# SAMW25_Xplained_Pro_triple_input_power_s.net
KiCad netlist of a schematic drawn in Altium Designer
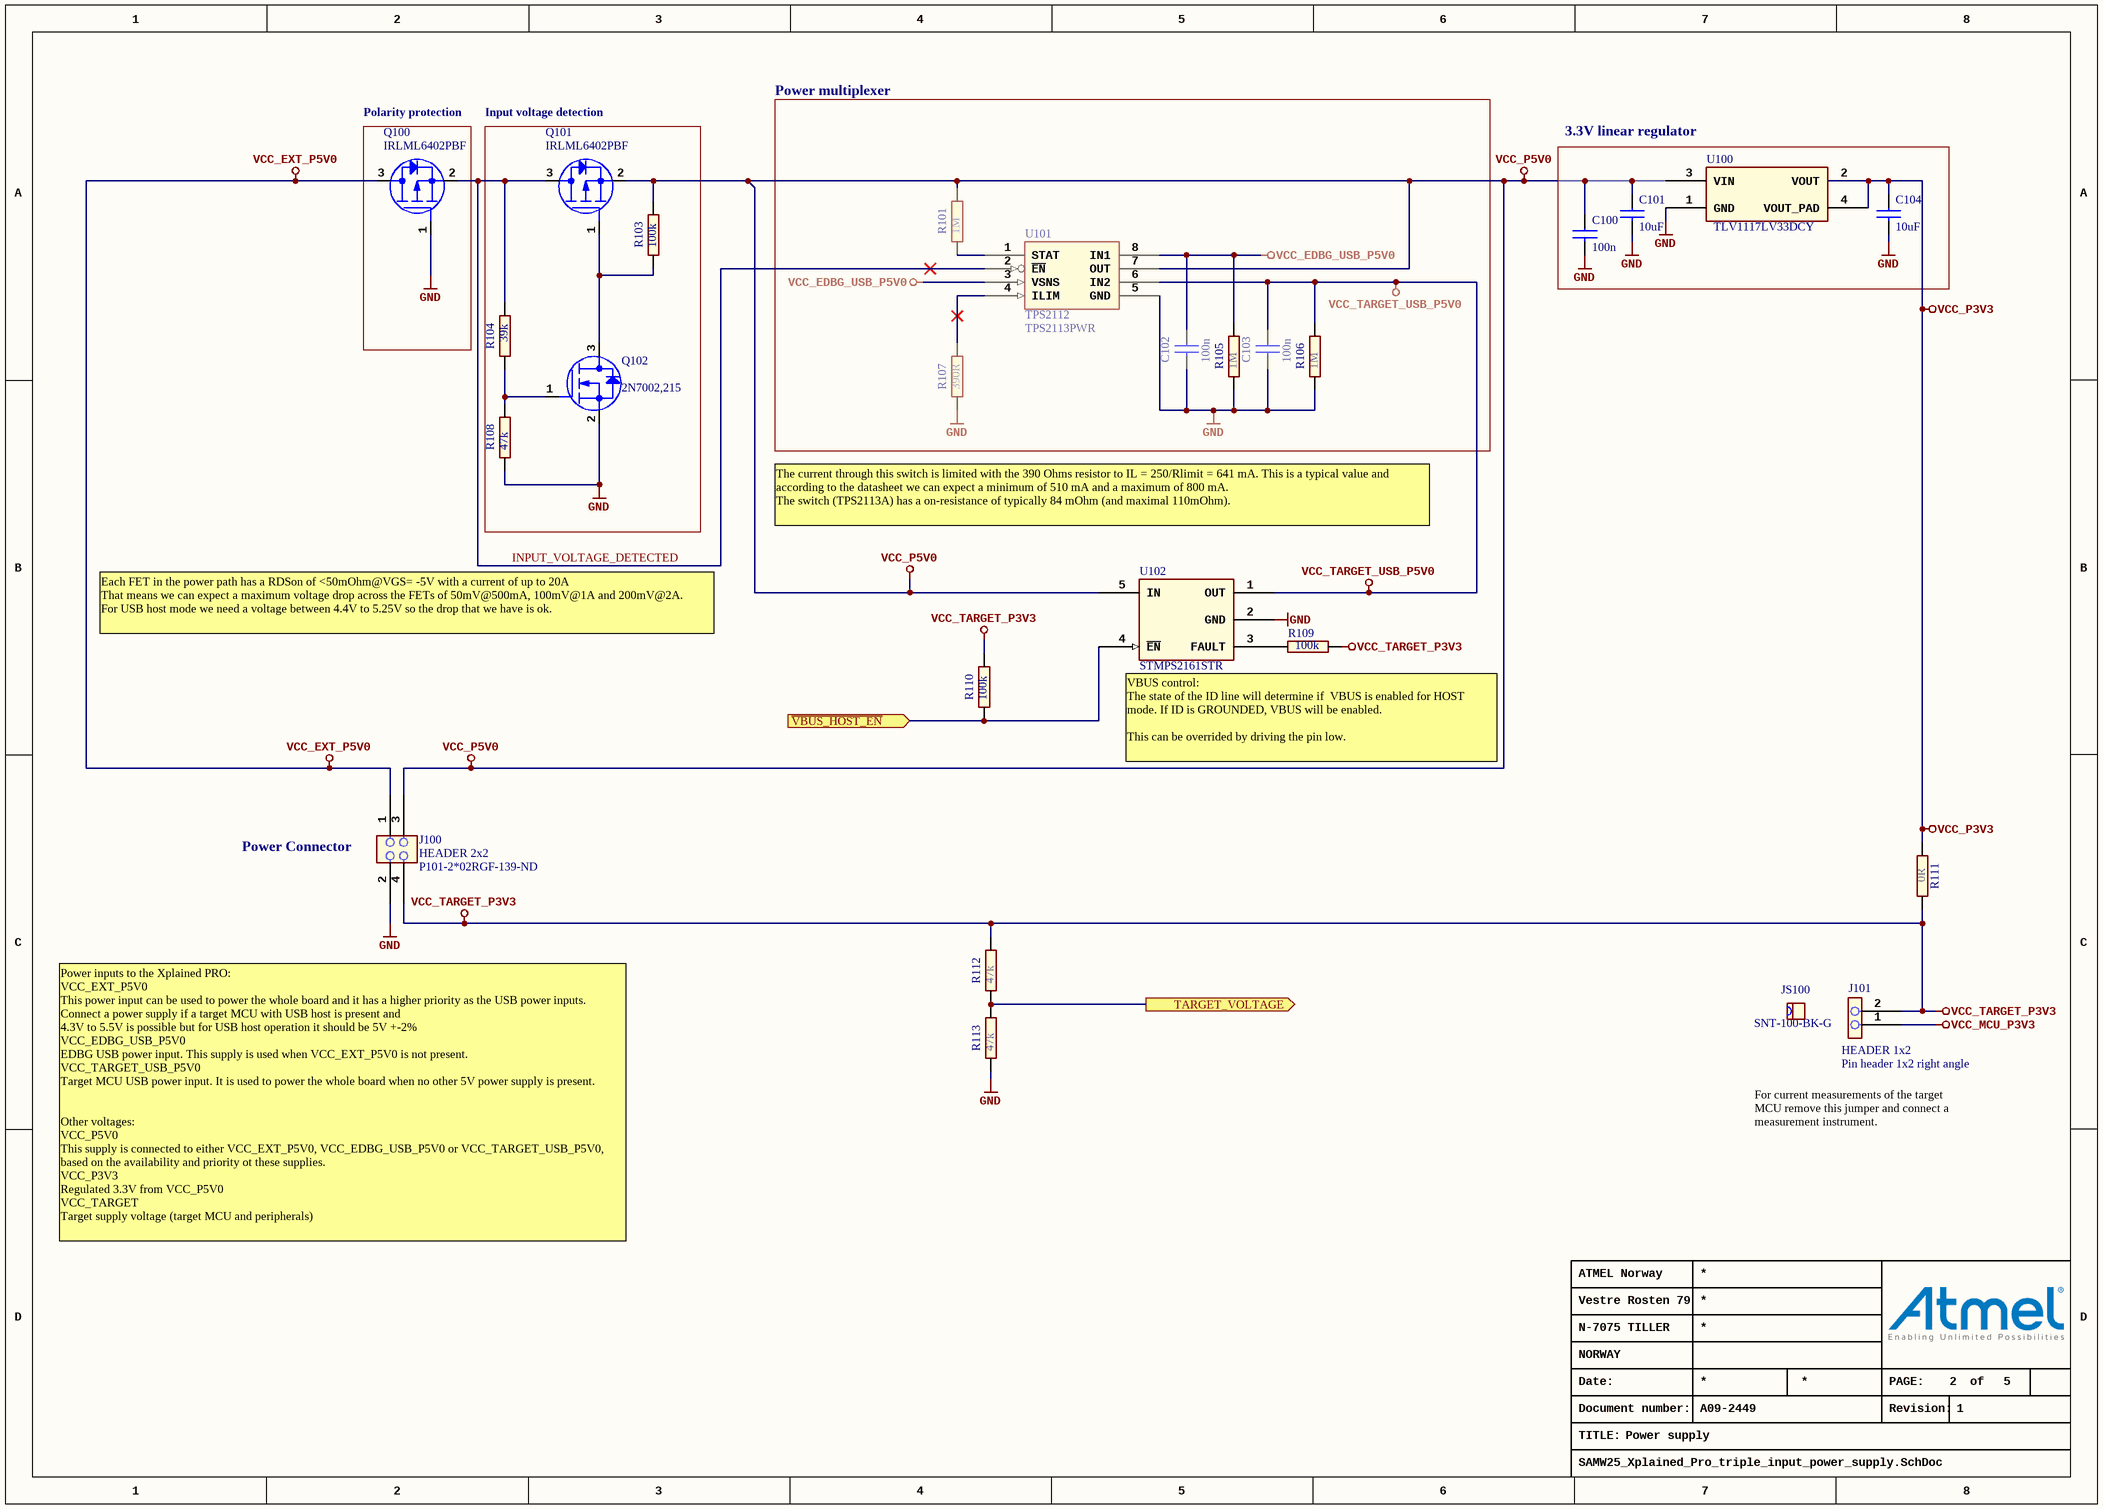
[diagram p0: SAMW25_Xplained_Pro_triple_input_power_supply.SchDoc]

(export (version "E")
  (design (tool "Eeschema 10.0.6"))
  (components
    (comp (ref "C100")
      (value "100n")
      (footprint "AP1-00001")
      (description "Ceramic capacitor, SMD 0402, X7R, 16V, +/-10%")
      (fields
        (field (name "TOLERANCE") "16V, +/-10%")
        (field (name "MANUFACTURER") "Kemet")
        (field (name "VERIFIED BY") "Lars Helge Mo")
      )
      (libsource (lib "AltiumDbLib") (part "CAP-NONPOL"))
    )
    (comp (ref "C101")
      (value "10uF")
      (footprint "AP1-00039")
      (description "Ceramic capacitor, SMD 0603, X5R, 16V, 10UF ± 20% (High Density)")
      (fields
        (field (name "TOLERANCE") "­± 20%")
        (field (name "MANUFACTURER") "Taiyo Yuden")
        (field (name "VERIFIED BY") "Lars Helge Mo")
      )
      (libsource (lib "AltiumDbLib") (part "CAP-NONPOL"))
    )
    (comp (ref "C102")
      (value "100n")
      (footprint "AP1-00053")
      (description "Ceramic capacitor, SMD 0402, X7R, 16V, +/-10%")
      (fields
        (field (name "TOLERANCE") "16V, +/-10%")
        (field (name "MANUFACTURER") "Kemet")
        (field (name "VERIFIED BY") "Lars Helge Mo")
      )
      (libsource (lib "AltiumDbLib") (part "CAP-NONPOL"))
    )
    (comp (ref "C103")
      (value "100n")
      (footprint "AP1-00053")
      (description "Ceramic capacitor, SMD 0402, X7R, 16V, +/-10%")
      (fields
        (field (name "TOLERANCE") "16V, +/-10%")
        (field (name "MANUFACTURER") "Kemet")
        (field (name "VERIFIED BY") "Lars Helge Mo")
      )
      (libsource (lib "AltiumDbLib") (part "CAP-NONPOL"))
    )
    (comp (ref "C104")
      (value "10uF")
      (footprint "AP1-00039")
      (description "Ceramic capacitor, SMD 0603, X5R, 16V, 10UF ± 20% (High Density)")
      (fields
        (field (name "TOLERANCE") "­± 20%")
        (field (name "MANUFACTURER") "Taiyo Yuden")
        (field (name "VERIFIED BY") "Lars Helge Mo")
      )
      (libsource (lib "AltiumDbLib") (part "CAP-NONPOL"))
    )
    (comp (ref "J100")
      (value "HEADER 2x2")
      (footprint "AP8-00628")
      (description "Pin header, 2x2, Right Angle, 2.54mm, THT, Pin In Paste")
      (fields
        (field (name "ALTIUM_VALUE") "P101-2*02RGF-139-ND")
        (field (name "MANUFACTURER") "Pro-data International Corp")
        (field (name "MPN") "P101-2*02RGF-139-ND")
        (field (name "VERIFIED BY") "Lars Helge Mo")
      )
      (libsource (lib "AltiumDbLib") (part "HEADER 2x2"))
    )
    (comp (ref "J101")
      (value "HEADER 1x2")
      (footprint "AP8-00367")
      (description "1x2 pin header, right angle, 2.54 mm pitch, through-hole")
      (fields
        (field (name "ALTIUM_VALUE") "Pin header 1x2 right angle")
        (field (name "MANUFACTURER") "Pro-data International Corp")
        (field (name "MPN") "2213R-2G")
        (field (name "VERIFIED BY") "Lars Helge")
      )
      (libsource (lib "AltiumDbLib") (part "HEADER 1x2"))
    )
    (comp (ref "JS100")
      (value "SNT-100-BK-G")
      (footprint "AP8-00525")
      (description "Jumper cap for 2.54mm pinheader")
      (fields
        (field (name "MANUFACTURER") "SAMTEC")
        (field (name "Comment") "To be used by request from ESCATEC")
        (field (name "VERIFIED BY") "Lars Helge Mo")
      )
      (libsource (lib "AltiumDbLib") (part "JUMPER_CAP"))
    )
    (comp (ref "Q100")
      (value "IRLML6402PBF")
      (footprint "AP5-00002")
      (description "P-ch. MOSFET. -30V, -3.7A continuous,RDS(ON)=0.05Ohm@VGS=-4,5V, RDS(ON)=0.08Ohm@VGS=-2.5V")
      (fields (field (name "MANUFACTURER") "International Rectifier") (field (name "Comment") "MOSFET_P_GSD"))
      (libsource (lib "AltiumDbLib") (part "MOSFET_P_GSD"))
    )
    (comp (ref "Q101")
      (value "IRLML6402PBF")
      (footprint "AP5-00002")
      (description "P-ch. MOSFET. -30V, -3.7A continuous,RDS(ON)=0.05Ohm@VGS=-4,5V, RDS(ON)=0.08Ohm@VGS=-2.5V")
      (fields (field (name "MANUFACTURER") "International Rectifier") (field (name "Comment") "MOSFET_P_GSD"))
      (libsource (lib "AltiumDbLib") (part "MOSFET_P_GSD"))
    )
    (comp (ref "Q102")
      (value "2N7002,215")
      (footprint "AP5-00002")
      (description "N-Channel MOSFET. 60V, 0.300A continuous, 1.2A Peak. RDS(ON) = 3.8Ohm@VGS=4.5V, VGS(th)<2.5V")
      (fields (field (name "MANUFACTURER") "NXP") (field (name "Comment") "MOSFET_N_GSD"))
      (libsource (lib "AltiumDbLib") (part "MOSFET_N_GSD"))
    )
    (comp (ref "R101")
      (value "1M")
      (footprint "AP2-00011")
      (description "Thick film resistor, SMD 0402, 1/16W, 1%")
      (fields
        (field (name "TOLERANCE") "1 %")
        (field (name "Comment") "R2")
        (field (name "VERIFIED BY") "Lars Helge Mo")
      )
      (libsource (lib "AltiumDbLib") (part "R2"))
    )
    (comp (ref "R103")
      (value "100k")
      (footprint "AP2-00011")
      (description "Thick film resistor, SMD 0402, 1/16W, 1%")
      (fields
        (field (name "TOLERANCE") "1 %")
        (field (name "Comment") "R2")
        (field (name "VERIFIED BY") "Lars Helge Mo")
      )
      (libsource (lib "AltiumDbLib") (part "R2"))
    )
    (comp (ref "R104")
      (value "39k")
      (footprint "AP2-00011")
      (description "Thick film resistor, SMD 0402, 1/16W, 1%")
      (fields
        (field (name "TOLERANCE") "1 %")
        (field (name "Comment") "R2")
        (field (name "VERIFIED BY") "Lars Helge Mo")
      )
      (libsource (lib "AltiumDbLib") (part "R2"))
    )
    (comp (ref "R105")
      (value "1M")
      (footprint "AP2-00011")
      (description "Thick film resistor, SMD 0402, 1/16W, 1%")
      (fields
        (field (name "TOLERANCE") "1 %")
        (field (name "Comment") "R2")
        (field (name "VERIFIED BY") "Lars Helge Mo")
      )
      (libsource (lib "AltiumDbLib") (part "R2"))
    )
    (comp (ref "R106")
      (value "1M")
      (footprint "AP2-00011")
      (description "Thick film resistor, SMD 0402, 1/16W, 1%")
      (fields
        (field (name "TOLERANCE") "1 %")
        (field (name "Comment") "R2")
        (field (name "VERIFIED BY") "Lars Helge Mo")
      )
      (libsource (lib "AltiumDbLib") (part "R2"))
    )
    (comp (ref "R107")
      (value "390R")
      (footprint "AP2-00011")
      (description "Thick film resistor, SMD 0402, 1/16W, 1%")
      (fields
        (field (name "TOLERANCE") "1 %")
        (field (name "Comment") "R2")
        (field (name "VERIFIED BY") "Lars Helge Mo")
      )
      (libsource (lib "AltiumDbLib") (part "R2"))
    )
    (comp (ref "R108")
      (value "47k")
      (footprint "AP2-00011")
      (description "Thick film resistor, SMD 0402, 1/16W, 1%")
      (fields
        (field (name "TOLERANCE") "1 %")
        (field (name "Comment") "R2")
        (field (name "VERIFIED BY") "Lars Helge Mo")
      )
      (libsource (lib "AltiumDbLib") (part "R2"))
    )
    (comp (ref "R109")
      (value "100k")
      (footprint "AP2-00011")
      (description "Thick film resistor, SMD 0402, 1/16W, 1%")
      (fields
        (field (name "TOLERANCE") "1 %")
        (field (name "Comment") "R2")
        (field (name "VERIFIED BY") "Lars Helge Mo")
      )
      (libsource (lib "") (part "R2_2"))
    )
    (comp (ref "R110")
      (value "100k")
      (footprint "AP2-00011")
      (description "Thick film resistor, SMD 0402, 1/16W, 1%")
      (fields
        (field (name "TOLERANCE") "1 %")
        (field (name "Comment") "R2")
        (field (name "VERIFIED BY") "Lars Helge Mo")
      )
      (libsource (lib "AltiumDbLib") (part "R2"))
    )
    (comp (ref "R111")
      (value "0R")
      (footprint "AP2-00011")
      (description "Thick film resistor, SMD 0402, 1/16W, 1%")
      (fields
        (field (name "TOLERANCE") "1 %")
        (field (name "Comment") "R2")
        (field (name "VERIFIED BY") "Lars Helge Mo")
      )
      (libsource (lib "") (part "R2_3"))
    )
    (comp (ref "R112")
      (value "47k")
      (footprint "AP2-00011")
      (description "Thick film resistor, SMD 0402, 1/16W, 1%")
      (fields
        (field (name "TOLERANCE") "1 %")
        (field (name "Comment") "R2")
        (field (name "VERIFIED BY") "Lars Helge Mo")
      )
      (libsource (lib "") (part "R2_1"))
    )
    (comp (ref "R113")
      (value "47k")
      (footprint "AP2-00011")
      (description "Thick film resistor, SMD 0402, 1/16W, 1%")
      (fields
        (field (name "TOLERANCE") "1 %")
        (field (name "Comment") "R2")
        (field (name "VERIFIED BY") "Lars Helge Mo")
      )
      (libsource (lib "") (part "R2_1"))
    )
    (comp (ref "U100")
      (value "TLV1117LV33DCY")
      (footprint "AP6-00399")
      (description "1-A, LDO (0.455V @ 1A), 3.3V out, 1.5% accuracy, 6.0V Vin max.")
      (fields (field (name "MANUFACTURER") "Texas Instruments") (field (name "MPN") "TLV1117LV33DCYR"))
      (libsource (lib "AltiumDbLib") (part "VOLTREG_SOT223_4"))
    )
    (comp (ref "U101")
      (value "TPS2112")
      (footprint "AP6-00054")
      (description "Autoswitching 2:1 Power Mux")
      (fields
        (field (name "ALTIUM_VALUE") "TPS2113PWR")
        (field (name "MANUFACTURER") "Texas Instruments")
        (field (name "MPN") "TPS2113PWR")
        (field (name "VERIFIED BY") "Sveinung Helgeland")
      )
      (libsource (lib "AltiumDbLib") (part "TPS2112"))
    )
    (comp (ref "U102")
      (value "STMPS2161STR")
      (footprint "AP6-00087")
      (description "Single channel power switch, 1A, reverse block, active low enabled.")
      (fields
        (field (name "TOLERANCE") "2.7 to 5.5V")
        (field (name "Comment") "STMPS2161")
        (field (name "VERIFIED BY") "*")
      )
      (libsource (lib "AltiumDbLib") (part "STMPS2161"))
    )
  )
  (nets
    (net (code "1") (name "/INPUT_VOLTAGE_DETECTED") (class "Default")
      (node (ref "Q100") (pin "2") (pinfunction "S_2") (pintype "passive"))
      (node (ref "Q101") (pin "3") (pinfunction "D_3") (pintype "passive"))
      (node (ref "R104") (pin "2") (pinfunction "2_2") (pintype "passive"))
      (node (ref "U101") (pin "2") (pinfunction "~{EN}_2") (pintype "input"))
    )
    (net (code "2") (name "/TARGET_VOLTAGE") (class "Default")
      (node (ref "R112") (pin "1") (pinfunction "1_1") (pintype "passive"))
      (node (ref "R113") (pin "2") (pinfunction "2_2") (pintype "passive"))
    )
    (net (code "3") (name "/~{VBUS_HOST_EN}") (class "Default")
      (node (ref "R110") (pin "1") (pinfunction "1_1") (pintype "passive"))
      (node (ref "U102") (pin "4") (pinfunction "~{EN}_4") (pintype "input"))
    )
    (net (code "4") (name "GND") (class "Default")
      (node (ref "C100") (pin "2") (pinfunction "2_2") (pintype "passive"))
      (node (ref "C101") (pin "2") (pinfunction "2_2") (pintype "passive"))
      (node (ref "C102") (pin "2") (pinfunction "2_2") (pintype "passive"))
      (node (ref "C103") (pin "2") (pinfunction "2_2") (pintype "passive"))
      (node (ref "C104") (pin "2") (pinfunction "2_2") (pintype "passive"))
      (node (ref "J100") (pin "2") (pinfunction "2_2") (pintype "passive"))
      (node (ref "Q100") (pin "1") (pinfunction "G_1") (pintype "passive"))
      (node (ref "Q102") (pin "2") (pinfunction "S_2") (pintype "passive"))
      (node (ref "R105") (pin "1") (pinfunction "1_1") (pintype "passive"))
      (node (ref "R106") (pin "1") (pinfunction "1_1") (pintype "passive"))
      (node (ref "R107") (pin "1") (pinfunction "1_1") (pintype "passive"))
      (node (ref "R108") (pin "1") (pinfunction "1_1") (pintype "passive"))
      (node (ref "R113") (pin "1") (pinfunction "1_1") (pintype "passive"))
      (node (ref "U100") (pin "1") (pinfunction "GND_1") (pintype "power_in"))
      (node (ref "U101") (pin "5") (pinfunction "GND_5") (pintype "power_in"))
      (node (ref "U102") (pin "2") (pinfunction "GND_2") (pintype "power_in"))
    )
    (net (code "5") (name "Net-(Q101-G)") (class "Default")
      (node (ref "Q101") (pin "1") (pinfunction "G_1") (pintype "passive"))
      (node (ref "Q102") (pin "3") (pinfunction "D_3") (pintype "passive"))
      (node (ref "R103") (pin "1") (pinfunction "1_1") (pintype "passive"))
    )
    (net (code "6") (name "Net-(Q102-G)") (class "Default")
      (node (ref "Q102") (pin "1") (pinfunction "G_1") (pintype "passive"))
      (node (ref "R104") (pin "1") (pinfunction "1_1") (pintype "passive"))
      (node (ref "R108") (pin "2") (pinfunction "2_2") (pintype "passive"))
    )
    (net (code "7") (name "Net-(U101-ILIM)") (class "Default")
      (node (ref "R107") (pin "2") (pinfunction "2_2") (pintype "passive"))
      (node (ref "U101") (pin "4") (pinfunction "ILIM_4") (pintype "input"))
    )
    (net (code "8") (name "Net-(U101-STAT)") (class "Default")
      (node (ref "R101") (pin "1") (pinfunction "1_1") (pintype "passive"))
      (node (ref "U101") (pin "1") (pinfunction "STAT_1") (pintype "open_collector"))
    )
    (net (code "9") (name "Net-(U102-FAULT)") (class "Default")
      (node (ref "R109") (pin "2") (pinfunction "2_2") (pintype "passive"))
      (node (ref "U102") (pin "3") (pinfunction "FAULT_3") (pintype "open_collector"))
    )
    (net (code "10") (name "VCC_EDBG_USB_P5V0") (class "Default")
      (node (ref "C102") (pin "1") (pinfunction "1_1") (pintype "passive"))
      (node (ref "R105") (pin "2") (pinfunction "2_2") (pintype "passive"))
      (node (ref "U101") (pin "3") (pinfunction "VSNS_3") (pintype "input"))
      (node (ref "U101") (pin "8") (pinfunction "IN1_8") (pintype "power_in"))
    )
    (net (code "11") (name "VCC_EXT_P5V0") (class "Default")
      (node (ref "J100") (pin "1") (pinfunction "1_1") (pintype "passive"))
      (node (ref "Q100") (pin "3") (pinfunction "D_3") (pintype "passive"))
    )
    (net (code "12") (name "VCC_MCU_P3V3") (class "Default")
      (node (ref "J101") (pin "1") (pinfunction "1_1") (pintype "passive"))
    )
    (net (code "13") (name "VCC_P3V3") (class "Default")
      (node (ref "C104") (pin "1") (pinfunction "1_1") (pintype "passive"))
      (node (ref "R111") (pin "1") (pinfunction "1_1") (pintype "passive"))
      (node (ref "U100") (pin "2") (pinfunction "VOUT_2") (pintype "power_in"))
      (node (ref "U100") (pin "4") (pinfunction "VOUT_PAD_4") (pintype "power_in"))
    )
    (net (code "14") (name "VCC_P5V0") (class "Default")
      (node (ref "C100") (pin "1") (pinfunction "1_1") (pintype "passive"))
      (node (ref "C101") (pin "1") (pinfunction "1_1") (pintype "passive"))
      (node (ref "J100") (pin "3") (pinfunction "3_3") (pintype "passive"))
      (node (ref "Q101") (pin "2") (pinfunction "S_2") (pintype "passive"))
      (node (ref "R101") (pin "2") (pinfunction "2_2") (pintype "passive"))
      (node (ref "R103") (pin "2") (pinfunction "2_2") (pintype "passive"))
      (node (ref "U100") (pin "3") (pinfunction "VIN_3") (pintype "power_in"))
      (node (ref "U101") (pin "7") (pinfunction "OUT_7") (pintype "power_in"))
      (node (ref "U102") (pin "5") (pinfunction "IN_5") (pintype "power_in"))
    )
    (net (code "15") (name "VCC_TARGET_P3V3") (class "Default")
      (node (ref "J100") (pin "4") (pinfunction "4_4") (pintype "passive"))
      (node (ref "J101") (pin "2") (pinfunction "2_2") (pintype "passive"))
      (node (ref "R109") (pin "1") (pinfunction "1_1") (pintype "passive"))
      (node (ref "R110") (pin "2") (pinfunction "2_2") (pintype "passive"))
      (node (ref "R111") (pin "2") (pinfunction "2_2") (pintype "passive"))
      (node (ref "R112") (pin "2") (pinfunction "2_2") (pintype "passive"))
    )
    (net (code "16") (name "VCC_TARGET_USB_P5V0") (class "Default")
      (node (ref "C103") (pin "1") (pinfunction "1_1") (pintype "passive"))
      (node (ref "R106") (pin "2") (pinfunction "2_2") (pintype "passive"))
      (node (ref "U101") (pin "6") (pinfunction "IN2_6") (pintype "power_in"))
      (node (ref "U102") (pin "1") (pinfunction "OUT_1") (pintype "power_in"))
    )
  )
)
